# Breakout.net
KiCad netlist of a schematic drawn in Altium Designer
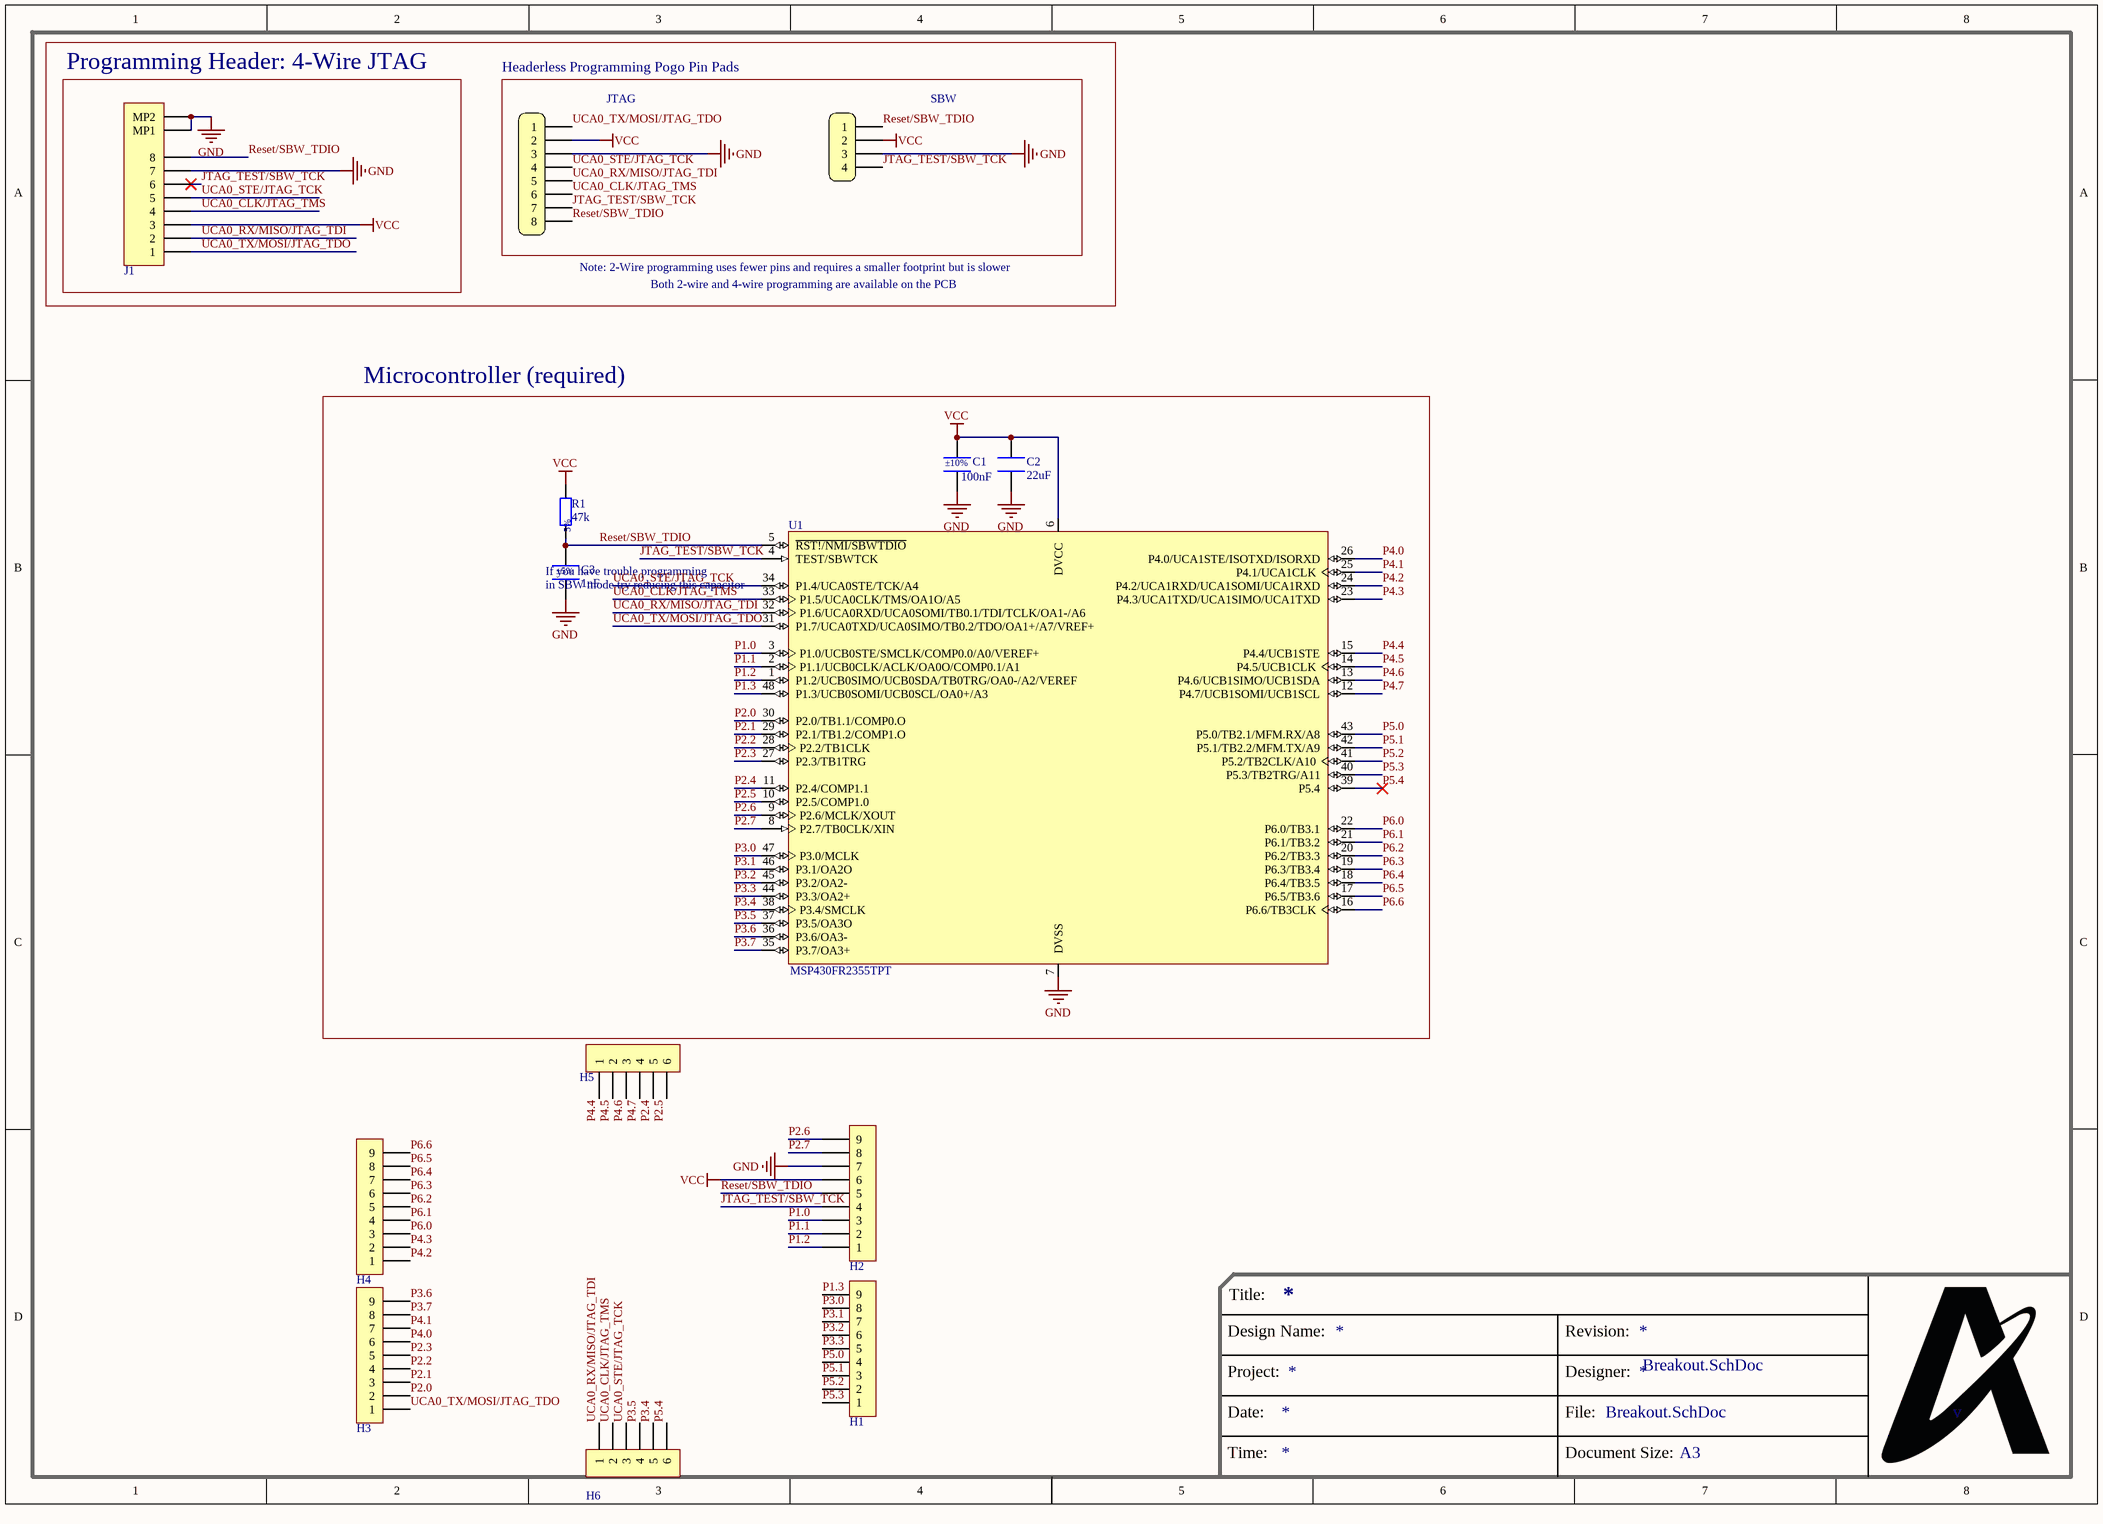
[diagram p0: Breakout.SchDoc]

(export (version "E")
  (design (tool "Eeschema 10.0.6"))
  (components
    (comp (ref "C1")
      (value "100nF")
      (footprint "APSS Generic Components:CAPACITOR_0805_2012M-70N")
      (description "Generic Capacitor")
      (fields (field (name "TOLERANCE") "±10%") (field (name "MF PART NO.") "C0805C104K5RAC7800"))
      (libsource (lib "General Components") (part "Generic Capacitor"))
    )
    (comp (ref "C2")
      (value "22uF")
      (footprint "APSS Prototype Parts:CAPACITOR_0805_2012M-70N")
      (description "Passive - Capacitor, X5R, 22uF Max, 6.3V, 0805 (2012 Metric), ±20%, -55°C ~ 85°C. 8.8uF @ 5V")
      (fields (field (name "TOLERANCE") "±20%") (field (name "MF PART NO.") "C0805C226M9PACTU"))
      (libsource (lib "APSS Prototype Parts") (part "C0805C226M9PACTU"))
    )
    (comp (ref "C3")
      (value "1nF")
      (footprint "APSS Generic Components:CAPACITOR_0805_2012M-70N")
      (description "Generic Capacitor")
      (fields (field (name "TOLERANCE") "±5%") (field (name "MF PART NO.") "399-C0805C102J5GAC7800CT-ND"))
      (libsource (lib "APSS Generic Components") (part "Generic Capacitor"))
    )
    (comp (ref "H*")
      (value "Headerless Pogo Holes 4-pin")
      (footprint "APSS Connectors:POGO_4_PIN_HEADER")
      (description "Connector - Pogo pin pads, 4-pin")
      (libsource (lib "APSS Connectors") (part "Headerless Pogo Holes 4-pin"))
    )
    (comp (ref "H1")
      (value "HDR,2.54mm,1x9")
      (footprint "APSS Connectors:HEADER_2.54MM_1x9PIN")
      (description "Connector - 2.54mm, 1x9-pin")
      (libsource (lib "") (part "HDR,2.54mm,1x9_1"))
    )
    (comp (ref "H2")
      (value "HDR,2.54mm,1x9")
      (footprint "APSS Connectors:HEADER_2.54MM_1x9PIN")
      (description "Connector - 2.54mm, 1x9-pin")
      (libsource (lib "") (part "HDR,2.54mm,1x9_1"))
    )
    (comp (ref "H3")
      (value "HDR,2.54mm,1x9")
      (footprint "APSS Connectors:HEADER_2.54MM_1x9PIN")
      (description "Connector - 2.54mm, 1x9-pin")
      (libsource (lib "APSS Connectors") (part "HDR,2.54mm,1x9"))
    )
    (comp (ref "H4")
      (value "HDR,2.54mm,1x9")
      (footprint "APSS Connectors:HEADER_2.54MM_1x9PIN")
      (description "Connector - 2.54mm, 1x9-pin")
      (libsource (lib "APSS Connectors") (part "HDR,2.54mm,1x9"))
    )
    (comp (ref "H5")
      (value "HDR,2.54mm,1x6")
      (footprint "APSS Connectors:HEADER_2.54MM_1x6PIN")
      (description "Connector - 2.54mm, 1x6-pin")
      (libsource (lib "") (part "HDR,2.54mm,1x6_1"))
    )
    (comp (ref "H6")
      (value "HDR,2.54mm,1x6")
      (footprint "APSS Connectors:HEADER_2.54MM_1x6PIN")
      (description "Connector - 2.54mm, 1x6-pin")
      (libsource (lib "APSS Connectors") (part "HDR,2.54mm,1x6"))
    )
    (comp (ref "J1")
      (value "5015680807")
      (footprint "APSS Connectors:MOLEX_5015680807")
      (description "Connector - Picoclasp  08-pin, SMT, RA")
      (fields (field (name "APSS STANDARD PART") "APSS Standard"))
      (libsource (lib "APSS Connectors") (part "5015680807"))
    )
    (comp (ref "PP2")
      (value "Headerless Pogo Holes 8-pin")
      (footprint "APSS Connectors:POGO_8_PIN_HEADER")
      (description "Connector - Pogo pin pads, 8-pin")
      (libsource (lib "APSS Connectors") (part "Headerless Pogo Holes 8-pin"))
    )
    (comp (ref "R1")
      (value "47k")
      (footprint "APSS Prototype Parts:Resistor_0805_2012M-50N")
      (fields
        (field (name "TOLERANCE") "5%")
        (field (name "POWER") "1/8W")
        (field (name "MF PART NO.") "RMCF0805JT47K0")
      )
      (libsource (lib "APSS Prototype Parts") (part "RMCF0805JT Series"))
    )
    (comp (ref "U1")
      (value "MSP430FR2355TPT")
      (footprint "APSS Prototype Parts:LQFP_PT_48_N")
      (fields (field (name "APSS STANDARD PART") "APSS Standard"))
      (libsource (lib "APSS Prototype Parts") (part "MSP430FR2355TPT"))
    )
  )
  (nets
    (net (code "1") (name "/JTAG_TEST{slash}SBW_TCK") (class "Default")
      (node (ref "H*") (pin "4") (pinfunction "4_4") (pintype "passive"))
      (node (ref "H2") (pin "4") (pinfunction "4_4") (pintype "passive"))
      (node (ref "J1") (pin "6") (pinfunction "6_6") (pintype "passive"))
      (node (ref "PP2") (pin "7") (pinfunction "7_7") (pintype "passive"))
      (node (ref "U1") (pin "4") (pinfunction "TEST/SBWTCK_4") (pintype "input"))
    )
    (net (code "2") (name "/P1.0") (class "Default")
      (node (ref "H2") (pin "3") (pinfunction "3_3") (pintype "passive"))
      (node (ref "U1") (pin "3") (pinfunction "P1.0/UCB0STE/SMCLK/COMP0.0/A0/VEREF+_3") (pintype "bidirectional"))
    )
    (net (code "3") (name "/P1.1") (class "Default")
      (node (ref "H2") (pin "2") (pinfunction "2_2") (pintype "passive"))
      (node (ref "U1") (pin "2") (pinfunction "P1.1/UCB0CLK/ACLK/OA0O/COMP0.1/A1_2") (pintype "bidirectional"))
    )
    (net (code "4") (name "/P1.2") (class "Default")
      (node (ref "H2") (pin "1") (pinfunction "1_1") (pintype "passive"))
      (node (ref "U1") (pin "1") (pinfunction "P1.2/UCB0SIMO/UCB0SDA/TB0TRG/OA0-/A2/VEREF_1") (pintype "bidirectional"))
    )
    (net (code "5") (name "/P1.3") (class "Default")
      (node (ref "H1") (pin "9") (pinfunction "9_9") (pintype "passive"))
      (node (ref "U1") (pin "48") (pinfunction "P1.3/UCB0SOMI/UCB0SCL/OA0+/A3_48") (pintype "bidirectional"))
    )
    (net (code "6") (name "/P2.0") (class "Default")
      (node (ref "H3") (pin "2") (pinfunction "2_2") (pintype "passive"))
      (node (ref "U1") (pin "30") (pinfunction "P2.0/TB1.1/COMP0.O_30") (pintype "bidirectional"))
    )
    (net (code "7") (name "/P2.1") (class "Default")
      (node (ref "H3") (pin "3") (pinfunction "3_3") (pintype "passive"))
      (node (ref "U1") (pin "29") (pinfunction "P2.1/TB1.2/COMP1.O_29") (pintype "bidirectional"))
    )
    (net (code "8") (name "/P2.2") (class "Default")
      (node (ref "H3") (pin "4") (pinfunction "4_4") (pintype "passive"))
      (node (ref "U1") (pin "28") (pinfunction "P2.2/TB1CLK_28") (pintype "bidirectional"))
    )
    (net (code "9") (name "/P2.3") (class "Default")
      (node (ref "H3") (pin "5") (pinfunction "5_5") (pintype "passive"))
      (node (ref "U1") (pin "27") (pinfunction "P2.3/TB1TRG_27") (pintype "bidirectional"))
    )
    (net (code "10") (name "/P2.4") (class "Default")
      (node (ref "H5") (pin "5") (pinfunction "5_5") (pintype "passive"))
      (node (ref "U1") (pin "11") (pinfunction "P2.4/COMP1.1_11") (pintype "bidirectional"))
    )
    (net (code "11") (name "/P2.5") (class "Default")
      (node (ref "H5") (pin "6") (pinfunction "6_6") (pintype "passive"))
      (node (ref "U1") (pin "10") (pinfunction "P2.5/COMP1.0_10") (pintype "bidirectional"))
    )
    (net (code "12") (name "/P2.6") (class "Default")
      (node (ref "H2") (pin "9") (pinfunction "9_9") (pintype "passive"))
      (node (ref "U1") (pin "9") (pinfunction "P2.6/MCLK/XOUT_9") (pintype "bidirectional"))
    )
    (net (code "13") (name "/P2.7") (class "Default")
      (node (ref "H2") (pin "8") (pinfunction "8_8") (pintype "passive"))
      (node (ref "U1") (pin "8") (pinfunction "P2.7/TB0CLK/XIN_8") (pintype "input"))
    )
    (net (code "14") (name "/P3.0") (class "Default")
      (node (ref "H1") (pin "8") (pinfunction "8_8") (pintype "passive"))
      (node (ref "U1") (pin "47") (pinfunction "P3.0/MCLK_47") (pintype "bidirectional"))
    )
    (net (code "15") (name "/P3.1") (class "Default")
      (node (ref "H1") (pin "7") (pinfunction "7_7") (pintype "passive"))
      (node (ref "U1") (pin "46") (pinfunction "P3.1/OA2O_46") (pintype "bidirectional"))
    )
    (net (code "16") (name "/P3.2") (class "Default")
      (node (ref "H1") (pin "6") (pinfunction "6_6") (pintype "passive"))
      (node (ref "U1") (pin "45") (pinfunction "P3.2/OA2-_45") (pintype "bidirectional"))
    )
    (net (code "17") (name "/P3.3") (class "Default")
      (node (ref "H1") (pin "5") (pinfunction "5_5") (pintype "passive"))
      (node (ref "U1") (pin "44") (pinfunction "P3.3/OA2+_44") (pintype "bidirectional"))
    )
    (net (code "18") (name "/P3.4") (class "Default")
      (node (ref "H6") (pin "5") (pinfunction "5_5") (pintype "passive"))
      (node (ref "U1") (pin "38") (pinfunction "P3.4/SMCLK_38") (pintype "bidirectional"))
    )
    (net (code "19") (name "/P3.5") (class "Default")
      (node (ref "H6") (pin "4") (pinfunction "4_4") (pintype "passive"))
      (node (ref "U1") (pin "37") (pinfunction "P3.5/OA3O_37") (pintype "bidirectional"))
    )
    (net (code "20") (name "/P3.6") (class "Default")
      (node (ref "H3") (pin "9") (pinfunction "9_9") (pintype "passive"))
      (node (ref "U1") (pin "36") (pinfunction "P3.6/OA3-_36") (pintype "bidirectional"))
    )
    (net (code "21") (name "/P3.7") (class "Default")
      (node (ref "H3") (pin "8") (pinfunction "8_8") (pintype "passive"))
      (node (ref "U1") (pin "35") (pinfunction "P3.7/OA3+_35") (pintype "bidirectional"))
    )
    (net (code "22") (name "/P4.0") (class "Default")
      (node (ref "H3") (pin "6") (pinfunction "6_6") (pintype "passive"))
      (node (ref "U1") (pin "26") (pinfunction "P4.0/UCA1STE/ISOTXD/ISORXD_26") (pintype "bidirectional"))
    )
    (net (code "23") (name "/P4.1") (class "Default")
      (node (ref "H3") (pin "7") (pinfunction "7_7") (pintype "passive"))
      (node (ref "U1") (pin "25") (pinfunction "P4.1/UCA1CLK_25") (pintype "bidirectional"))
    )
    (net (code "24") (name "/P4.2") (class "Default")
      (node (ref "H4") (pin "1") (pinfunction "1_1") (pintype "passive"))
      (node (ref "U1") (pin "24") (pinfunction "P4.2/UCA1RXD/UCA1SOMI/UCA1RXD_24") (pintype "bidirectional"))
    )
    (net (code "25") (name "/P4.3") (class "Default")
      (node (ref "H4") (pin "2") (pinfunction "2_2") (pintype "passive"))
      (node (ref "U1") (pin "23") (pinfunction "P4.3/UCA1TXD/UCA1SIMO/UCA1TXD_23") (pintype "bidirectional"))
    )
    (net (code "26") (name "/P4.4") (class "Default")
      (node (ref "H5") (pin "1") (pinfunction "1_1") (pintype "passive"))
      (node (ref "U1") (pin "15") (pinfunction "P4.4/UCB1STE_15") (pintype "bidirectional"))
    )
    (net (code "27") (name "/P4.5") (class "Default")
      (node (ref "H5") (pin "2") (pinfunction "2_2") (pintype "passive"))
      (node (ref "U1") (pin "14") (pinfunction "P4.5/UCB1CLK_14") (pintype "bidirectional"))
    )
    (net (code "28") (name "/P4.6") (class "Default")
      (node (ref "H5") (pin "3") (pinfunction "3_3") (pintype "passive"))
      (node (ref "U1") (pin "13") (pinfunction "P4.6/UCB1SIMO/UCB1SDA_13") (pintype "bidirectional"))
    )
    (net (code "29") (name "/P4.7") (class "Default")
      (node (ref "H5") (pin "4") (pinfunction "4_4") (pintype "passive"))
      (node (ref "U1") (pin "12") (pinfunction "P4.7/UCB1SOMI/UCB1SCL_12") (pintype "bidirectional"))
    )
    (net (code "30") (name "/P5.0") (class "Default")
      (node (ref "H1") (pin "4") (pinfunction "4_4") (pintype "passive"))
      (node (ref "U1") (pin "43") (pinfunction "P5.0/TB2.1/MFM.RX/A8_43") (pintype "bidirectional"))
    )
    (net (code "31") (name "/P5.1") (class "Default")
      (node (ref "H1") (pin "3") (pinfunction "3_3") (pintype "passive"))
      (node (ref "U1") (pin "42") (pinfunction "P5.1/TB2.2/MFM.TX/A9_42") (pintype "bidirectional"))
    )
    (net (code "32") (name "/P5.2") (class "Default")
      (node (ref "H1") (pin "2") (pinfunction "2_2") (pintype "passive"))
      (node (ref "U1") (pin "41") (pinfunction "P5.2/TB2CLK/A10_41") (pintype "bidirectional"))
    )
    (net (code "33") (name "/P5.3") (class "Default")
      (node (ref "H1") (pin "1") (pinfunction "1_1") (pintype "passive"))
      (node (ref "U1") (pin "40") (pinfunction "P5.3/TB2TRG/A11_40") (pintype "bidirectional"))
    )
    (net (code "34") (name "/P5.4") (class "Default")
      (node (ref "H6") (pin "6") (pinfunction "6_6") (pintype "passive"))
      (node (ref "U1") (pin "39") (pinfunction "P5.4_39") (pintype "bidirectional"))
    )
    (net (code "35") (name "/P6.0") (class "Default")
      (node (ref "H4") (pin "3") (pinfunction "3_3") (pintype "passive"))
      (node (ref "U1") (pin "22") (pinfunction "P6.0/TB3.1_22") (pintype "bidirectional"))
    )
    (net (code "36") (name "/P6.1") (class "Default")
      (node (ref "H4") (pin "4") (pinfunction "4_4") (pintype "passive"))
      (node (ref "U1") (pin "21") (pinfunction "P6.1/TB3.2_21") (pintype "bidirectional"))
    )
    (net (code "37") (name "/P6.2") (class "Default")
      (node (ref "H4") (pin "5") (pinfunction "5_5") (pintype "passive"))
      (node (ref "U1") (pin "20") (pinfunction "P6.2/TB3.3_20") (pintype "bidirectional"))
    )
    (net (code "38") (name "/P6.3") (class "Default")
      (node (ref "H4") (pin "6") (pinfunction "6_6") (pintype "passive"))
      (node (ref "U1") (pin "19") (pinfunction "P6.3/TB3.4_19") (pintype "bidirectional"))
    )
    (net (code "39") (name "/P6.4") (class "Default")
      (node (ref "H4") (pin "7") (pinfunction "7_7") (pintype "passive"))
      (node (ref "U1") (pin "18") (pinfunction "P6.4/TB3.5_18") (pintype "bidirectional"))
    )
    (net (code "40") (name "/P6.5") (class "Default")
      (node (ref "H4") (pin "8") (pinfunction "8_8") (pintype "passive"))
      (node (ref "U1") (pin "17") (pinfunction "P6.5/TB3.6_17") (pintype "bidirectional"))
    )
    (net (code "41") (name "/P6.6") (class "Default")
      (node (ref "H4") (pin "9") (pinfunction "9_9") (pintype "passive"))
      (node (ref "U1") (pin "16") (pinfunction "P6.6/TB3CLK_16") (pintype "bidirectional"))
    )
    (net (code "42") (name "/Reset{slash}SBW_TDIO") (class "Default")
      (node (ref "C3") (pin "2") (pinfunction "2_2") (pintype "passive"))
      (node (ref "H*") (pin "1") (pinfunction "1_1") (pintype "passive"))
      (node (ref "H2") (pin "5") (pinfunction "5_5") (pintype "passive"))
      (node (ref "J1") (pin "8") (pinfunction "8_8") (pintype "passive"))
      (node (ref "PP2") (pin "8") (pinfunction "8_8") (pintype "passive"))
      (node (ref "R1") (pin "1") (pinfunction "1_1") (pintype "passive"))
      (node (ref "U1") (pin "5") (pinfunction "~{RST!/NMI/SBWTDIO}_5") (pintype "bidirectional"))
    )
    (net (code "43") (name "/UCA0_CLK{slash}JTAG_TMS") (class "Default")
      (node (ref "H6") (pin "2") (pinfunction "2_2") (pintype "passive"))
      (node (ref "J1") (pin "4") (pinfunction "4_4") (pintype "passive"))
      (node (ref "PP2") (pin "6") (pinfunction "6_6") (pintype "passive"))
      (node (ref "U1") (pin "33") (pinfunction "P1.5/UCA0CLK/TMS/OA1O/A5_33") (pintype "bidirectional"))
    )
    (net (code "44") (name "/UCA0_RX{slash}MISO{slash}JTAG_TDI") (class "Default")
      (node (ref "H6") (pin "1") (pinfunction "1_1") (pintype "passive"))
      (node (ref "J1") (pin "2") (pinfunction "2_2") (pintype "passive"))
      (node (ref "PP2") (pin "5") (pinfunction "5_5") (pintype "passive"))
      (node (ref "U1") (pin "32") (pinfunction "P1.6/UCA0RXD/UCA0SOMI/TB0.1/TDI/TCLK/OA1-/A6_32") (pintype "bidirectional"))
    )
    (net (code "45") (name "/UCA0_STE{slash}JTAG_TCK") (class "Default")
      (node (ref "H6") (pin "3") (pinfunction "3_3") (pintype "passive"))
      (node (ref "J1") (pin "5") (pinfunction "5_5") (pintype "passive"))
      (node (ref "PP2") (pin "4") (pinfunction "4_4") (pintype "passive"))
      (node (ref "U1") (pin "34") (pinfunction "P1.4/UCA0STE/TCK/A4_34") (pintype "bidirectional"))
    )
    (net (code "46") (name "/UCA0_TX{slash}MOSI{slash}JTAG_TDO") (class "Default")
      (node (ref "H3") (pin "1") (pinfunction "1_1") (pintype "passive"))
      (node (ref "J1") (pin "1") (pinfunction "1_1") (pintype "passive"))
      (node (ref "PP2") (pin "1") (pinfunction "1_1") (pintype "passive"))
      (node (ref "U1") (pin "31") (pinfunction "P1.7/UCA0TXD/UCA0SIMO/TB0.2/TDO/OA1+/A7/VREF+_31") (pintype "bidirectional"))
    )
    (net (code "47") (name "GND") (class "Default")
      (node (ref "C1") (pin "1") (pinfunction "1_1") (pintype "passive"))
      (node (ref "C2") (pin "1") (pinfunction "1_1") (pintype "passive"))
      (node (ref "C3") (pin "1") (pinfunction "1_1") (pintype "passive"))
      (node (ref "H*") (pin "3") (pinfunction "3_3") (pintype "passive"))
      (node (ref "H2") (pin "7") (pinfunction "7_7") (pintype "passive"))
      (node (ref "J1") (pin "7") (pinfunction "7_7") (pintype "passive"))
      (node (ref "J1") (pin "MP1") (pinfunction "MP1_MP1") (pintype "passive"))
      (node (ref "J1") (pin "MP2") (pinfunction "MP2_MP2") (pintype "passive"))
      (node (ref "PP2") (pin "3") (pinfunction "3_3") (pintype "passive"))
      (node (ref "U1") (pin "7") (pinfunction "DVSS_7") (pintype "power_in"))
    )
    (net (code "48") (name "VCC") (class "Default")
      (node (ref "C1") (pin "2") (pinfunction "2_2") (pintype "passive"))
      (node (ref "C2") (pin "2") (pinfunction "2_2") (pintype "passive"))
      (node (ref "H*") (pin "2") (pinfunction "2_2") (pintype "passive"))
      (node (ref "H2") (pin "6") (pinfunction "6_6") (pintype "passive"))
      (node (ref "J1") (pin "3") (pinfunction "3_3") (pintype "passive"))
      (node (ref "PP2") (pin "2") (pinfunction "2_2") (pintype "passive"))
      (node (ref "R1") (pin "2") (pinfunction "2_2") (pintype "passive"))
      (node (ref "U1") (pin "6") (pinfunction "DVCC_6") (pintype "power_in"))
    )
  )
)
